# ProPrj_HydromatMK1_2025-12-27_13-47-41_2.net
KiCad netlist of a schematic drawn in EasyEDA Pro
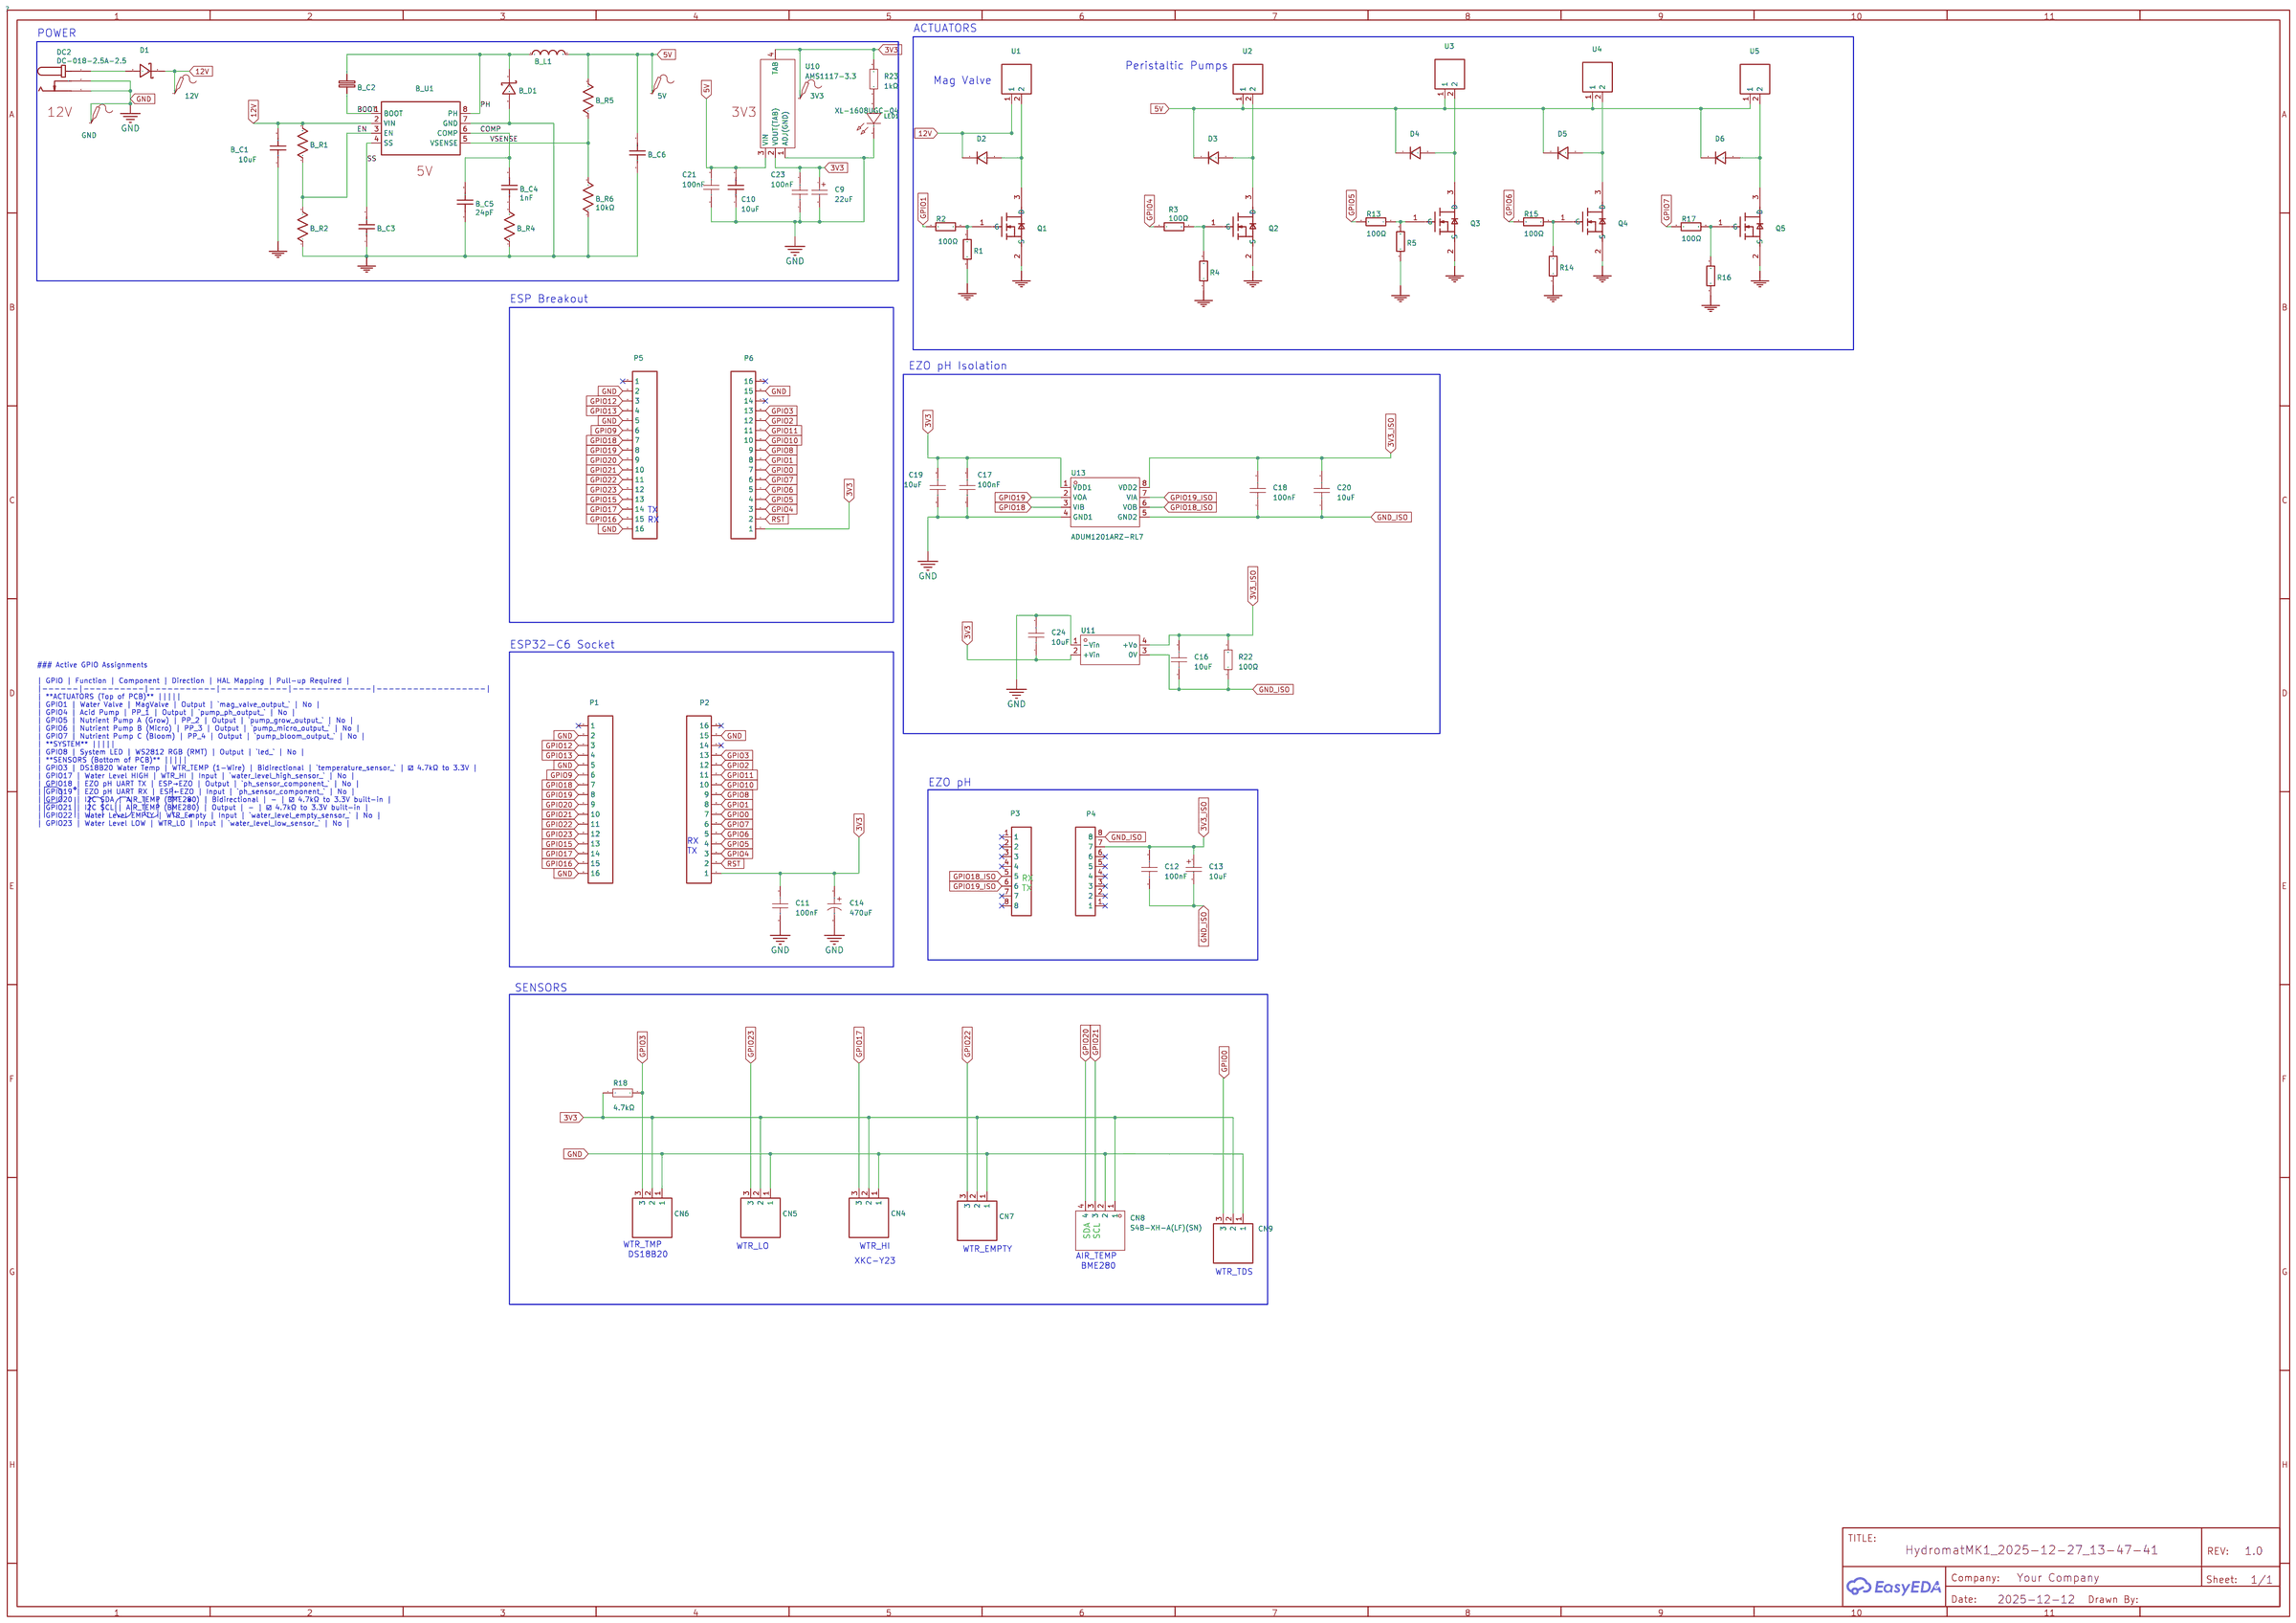
[diagram p0: schematic sheet]

(export (version "E")
  (design (tool "Eeschema 10.0.6"))
  (components
    (comp (ref "3V3")
      (value "5017")
      (footprint "easyedapro:Test-Point-0.5mm")
      (description "Test Point 测试点")
      (libsource (lib "easyedapro") (part "Test-Point"))
    )
    (comp (ref "5V")
      (value "5017")
      (footprint "easyedapro:Test-Point-0.5mm")
      (description "Test Point 测试点")
      (libsource (lib "easyedapro") (part "Test-Point"))
    )
    (comp (ref "12V")
      (value "5017")
      (footprint "easyedapro:Test-Point-0.5mm")
      (description "Test Point 测试点")
      (libsource (lib "easyedapro") (part "Test-Point"))
    )
    (comp (ref "B_C1")
      (value "10uF")
      (footprint "easyedapro:C0805")
      (fields
        (field (name "Manufacturer Part") "CL21A106KAYNNNE")
        (field (name "Manufacturer") "SAMSUNG(三星)")
      )
      (libsource (lib "easyedapro") (part "10uF"))
    )
    (comp (ref "B_C2")
      (value "100nF")
      (footprint "easyedapro:C0402")
      (fields (field (name "Manufacturer Part") "GRM155R71A104KA01D") (field (name "Manufacturer") "MuRata"))
      (libsource (lib "easyedapro") (part "100nF"))
    )
    (comp (ref "B_C3")
      (value "8.2nF")
      (footprint "easyedapro:C0201")
      (fields
        (field (name "Manufacturer Part") "GRM033R71A822KA01D")
        (field (name "Manufacturer") "MuRata")
        (field (name "Contributor") "LCEDA_Lib")
      )
      (libsource (lib "easyedapro") (part "8.2nF"))
    )
    (comp (ref "B_C4")
      (value "1nF")
      (footprint "easyedapro:C0805")
      (fields (field (name "Manufacturer Part") "GRM1555C1H102JA01J") (field (name "Manufacturer") "MuRata"))
      (libsource (lib "easyedapro") (part "1nF"))
    )
    (comp (ref "B_C5")
      (value "24pF")
      (footprint "easyedapro:C0805")
      (fields
        (field (name "Manufacturer Part") "CL21C240JBANNNC")
        (field (name "Manufacturer") "Samsung Electro-Mechanics")
      )
      (libsource (lib "easyedapro") (part "24pF"))
    )
    (comp (ref "B_C6")
      (value "10uF")
      (footprint "easyedapro:C1206")
      (fields
        (field (name "Manufacturer Part") "GRM31CR61C106KA88L")
        (field (name "Manufacturer") "MuRata")
        (field (name "Contributor") "LCEDA_Lib")
      )
      (libsource (lib "easyedapro") (part "10 uF"))
    )
    (comp (ref "B_D1")
      (value "SS24FL")
      (footprint "easyedapro:SOD-123_L2.6-W1.6-LS3.5-RD")
      (fields (field (name "Manufacturer") "KEXIN(科信)") (field (name "Contributor") "LCSC"))
      (libsource (lib "easyedapro") (part "SS24FL_C489144"))
    )
    (comp (ref "B_L1")
      (value "6.8uH")
      (footprint "easyedapro:L0805")
      (fields
        (field (name "Manufacturer Part") "74436410680")
        (field (name "Manufacturer") "Wurth Electronik")
        (field (name "Contributor") "LCEDA_Lib")
      )
      (libsource (lib "easyedapro") (part "6.8 uH"))
    )
    (comp (ref "B_R1")
      (value "169kΩ")
      (footprint "easyedapro:R0402")
      (fields
        (field (name "Manufacturer Part") "CRCW0402169KFKED")
        (field (name "Manufacturer") "Vishay-Dale")
        (field (name "Contributor") "LCEDA_Lib")
      )
      (libsource (lib "easyedapro") (part "169K"))
    )
    (comp (ref "B_R2")
      (value "39.2kΩ")
      (footprint "easyedapro:R0402")
      (fields
        (field (name "Manufacturer Part") "CRCW040239K2FKED")
        (field (name "Manufacturer") "Vishay-Dale")
        (field (name "Contributor") "LCEDA_Lib")
      )
      (libsource (lib "easyedapro") (part "39K2"))
    )
    (comp (ref "B_R4")
      (value "45.3kΩ")
      (footprint "easyedapro:R0402")
      (fields
        (field (name "Manufacturer Part") "CRCW040245K3FKED")
        (field (name "Manufacturer") "Vishay-Dale")
        (field (name "Contributor") "LCEDA_Lib")
      )
      (libsource (lib "easyedapro") (part "45K3"))
    )
    (comp (ref "B_R5")
      (value "10.2kΩ")
      (footprint "easyedapro:R0402")
      (fields
        (field (name "Manufacturer Part") "CRCW040210K2FKED")
        (field (name "Manufacturer") "Vishay-Dale")
        (field (name "Contributor") "LCEDA_Lib")
      )
      (libsource (lib "easyedapro") (part "10K2"))
    )
    (comp (ref "B_R6")
      (value "10kΩ")
      (footprint "easyedapro:R0805")
      (fields
        (field (name "Manufacturer Part") "CRCW040210K2FKED")
        (field (name "Manufacturer") "Vishay-Dale")
      )
      (libsource (lib "easyedapro") (part "1K87"))
    )
    (comp (ref "B_U1")
      (value "TPS54232DR")
      (footprint "easyedapro:SOIC-8_L4.9-W3.9-P1.27-LS6.0-BL")
      (fields (field (name "Manufacturer") "TI") (field (name "Contributor") "LCSC"))
      (libsource (lib "easyedapro") (part "TPS54232DR"))
    )
    (comp (ref "C9")
      (value "22uF")
      (footprint "easyedapro:CASE-B_3528")
      (fields (field (name "Manufacturer Part") "TAJB226K016RNJ") (field (name "Manufacturer") "Kyocera AVX"))
      (libsource (lib "easyedapro") (part "TAJB226K016RNJ"))
    )
    (comp (ref "C10")
      (value "10uF")
      (footprint "easyedapro:C0805")
      (fields
        (field (name "Manufacturer Part") "CL21A106KAYNNNE")
        (field (name "Manufacturer") "SAMSUNG(三星)")
      )
      (libsource (lib "easyedapro") (part "10uF"))
    )
    (comp (ref "C11")
      (value "100nF")
      (footprint "easyedapro:C0603")
      (description "Capacitance:100nF Tolerance:±10% Tolerance:±10% Voltage Rating:50V Temperature Coefficient:X7R")
      (fields
        (field (name "Manufacturer Part") "CC0805KRX7R9BB104")
        (field (name "Manufacturer") "YAGEO(国巨)")
      )
      (libsource (lib "easyedapro") (part "CC0603KRX7R9BB104"))
    )
    (comp (ref "C12")
      (value "100nF")
      (footprint "easyedapro:C0603")
      (description "Capacitance:100nF Tolerance:±10% Tolerance:±10% Voltage Rating:50V Temperature Coefficient:X7R")
      (fields
        (field (name "Manufacturer Part") "CC0805KRX7R9BB104")
        (field (name "Manufacturer") "YAGEO(国巨)")
      )
      (libsource (lib "easyedapro") (part "CC0603KRX7R9BB104"))
    )
    (comp (ref "C13")
      (value "10uF")
      (footprint "easyedapro:CAP-SMD_L3.2-W1.6-RD-C7171")
      (fields (field (name "Manufacturer Part") "TAJA106K016RNJ") (field (name "Manufacturer") "Kyocera AVX"))
      (libsource (lib "easyedapro") (part "TAJA106K016RNJ"))
    )
    (comp (ref "C14")
      (value "470uF")
      (footprint "easyedapro:CAP-SMD_BD6.3-L6.6-W6.6-LS7.6-RD")
      (fields (field (name "Manufacturer Part") "RVT1E471M1010") (field (name "Manufacturer") "HONOR(荣誉)"))
      (libsource (lib "easyedapro") (part "RVT1C471M0607"))
    )
    (comp (ref "C16")
      (value "10uF")
      (footprint "easyedapro:C0805")
      (fields
        (field (name "Manufacturer Part") "GRM21BR71A106KE51L")
        (field (name "Manufacturer") "muRata(村田)")
      )
      (libsource (lib "easyedapro") (part "GRM21BR71A106KE51L"))
    )
    (comp (ref "C17")
      (value "100nF")
      (footprint "easyedapro:C0603")
      (description "Capacitance:100nF Tolerance:±10% Tolerance:±10% Voltage Rating:50V Temperature Coefficient:X7R")
      (fields
        (field (name "Manufacturer Part") "CC0805KRX7R9BB104")
        (field (name "Manufacturer") "YAGEO(国巨)")
      )
      (libsource (lib "easyedapro") (part "CC0603KRX7R9BB104"))
    )
    (comp (ref "C18")
      (value "100nF")
      (footprint "easyedapro:C0603")
      (description "Capacitance:100nF Tolerance:±10% Tolerance:±10% Voltage Rating:50V Temperature Coefficient:X7R")
      (fields
        (field (name "Manufacturer Part") "CC0805KRX7R9BB104")
        (field (name "Manufacturer") "YAGEO(国巨)")
      )
      (libsource (lib "easyedapro") (part "CC0603KRX7R9BB104"))
    )
    (comp (ref "C19")
      (value "10uF")
      (footprint "easyedapro:C0805")
      (fields
        (field (name "Manufacturer Part") "GRM21BR71A106KE51L")
        (field (name "Manufacturer") "muRata(村田)")
      )
      (libsource (lib "easyedapro") (part "GRM21BR71A106KE51L"))
    )
    (comp (ref "C20")
      (value "10uF")
      (footprint "easyedapro:C0805")
      (fields
        (field (name "Manufacturer Part") "GRM21BR71A106KE51L")
        (field (name "Manufacturer") "muRata(村田)")
      )
      (libsource (lib "easyedapro") (part "GRM21BR71A106KE51L"))
    )
    (comp (ref "C21")
      (value "100nF")
      (footprint "easyedapro:C0603")
      (description "Capacitance:100nF Tolerance:±10% Tolerance:±10% Voltage Rating:50V Temperature Coefficient:X7R")
      (fields
        (field (name "Manufacturer Part") "CC0805KRX7R9BB104")
        (field (name "Manufacturer") "YAGEO(国巨)")
      )
      (libsource (lib "easyedapro") (part "CC0603KRX7R9BB104"))
    )
    (comp (ref "C23")
      (value "100nF")
      (footprint "easyedapro:C0603")
      (description "Capacitance:100nF Tolerance:±10% Tolerance:±10% Voltage Rating:50V Temperature Coefficient:X7R")
      (fields
        (field (name "Manufacturer Part") "CC0805KRX7R9BB104")
        (field (name "Manufacturer") "YAGEO(国巨)")
      )
      (libsource (lib "easyedapro") (part "CC0603KRX7R9BB104"))
    )
    (comp (ref "C24")
      (value "10uF")
      (footprint "easyedapro:C0805")
      (fields
        (field (name "Manufacturer Part") "GRM21BR71A106KE51L")
        (field (name "Manufacturer") "muRata(村田)")
      )
      (libsource (lib "easyedapro") (part "GRM21BR71A106KE51L"))
    )
    (comp (ref "CN4")
      (value "S3B-XH-A-1(LF)(SN)")
      (footprint "easyedapro:CONN-TH_S3B-XH-A-LF-SN")
      (fields
        (field (name "Manufacturer Part") "S3B-XH-A(LF)(SN)")
        (field (name "Manufacturer") "JST")
        (field (name "Contributor") "LCSC")
      )
      (libsource (lib "easyedapro") (part "S3B-XH-A (LF)(SN)"))
    )
    (comp (ref "CN5")
      (value "S3B-XH-A-1(LF)(SN)")
      (footprint "easyedapro:CONN-TH_S3B-XH-A-LF-SN")
      (fields
        (field (name "Manufacturer Part") "S3B-XH-A(LF)(SN)")
        (field (name "Manufacturer") "JST")
        (field (name "Contributor") "LCSC")
      )
      (libsource (lib "easyedapro") (part "S3B-XH-A (LF)(SN)"))
    )
    (comp (ref "CN6")
      (value "S3B-XH-A-1(LF)(SN)")
      (footprint "easyedapro:CONN-TH_S3B-XH-A-LF-SN")
      (fields
        (field (name "Manufacturer Part") "S3B-XH-A(LF)(SN)")
        (field (name "Manufacturer") "JST")
        (field (name "Contributor") "LCSC")
      )
      (libsource (lib "easyedapro") (part "S3B-XH-A (LF)(SN)"))
    )
    (comp (ref "CN7")
      (value "S3B-XH-A-1(LF)(SN)")
      (footprint "easyedapro:CONN-TH_S3B-XH-A-LF-SN")
      (fields
        (field (name "Manufacturer Part") "S3B-XH-A(LF)(SN)")
        (field (name "Manufacturer") "JST")
        (field (name "Contributor") "LCSC")
      )
      (libsource (lib "easyedapro") (part "S3B-XH-A (LF)(SN)"))
    )
    (comp (ref "CN8")
      (value "S4B-XH-A(LF)(SN)")
      (footprint "easyedapro:CONN-TH_S4B-XH-A-LF-SN")
      (fields (field (name "Manufacturer") "JST"))
      (libsource (lib "easyedapro") (part "S4B-XH-A (LF)(SN)"))
    )
    (comp (ref "CN9")
      (value "S3B-XH-A-1(LF)(SN)")
      (footprint "easyedapro:CONN-TH_S3B-XH-A-LF-SN")
      (fields
        (field (name "Manufacturer Part") "S3B-XH-A(LF)(SN)")
        (field (name "Manufacturer") "JST")
        (field (name "Contributor") "LCSC")
      )
      (libsource (lib "easyedapro") (part "S3B-XH-A (LF)(SN)"))
    )
    (comp (ref "D1")
      (value "SS54")
      (footprint "easyedapro:SMB_L4.6-W3.6-LS5.3-RD")
      (fields
        (field (name "Manufacturer Part") "MBRS140T3G")
        (field (name "Manufacturer") "onsemi(安森美)")
        (field (name "Contributor") "LCSC")
      )
      (libsource (lib "easyedapro") (part "MBRS140T3G"))
    )
    (comp (ref "D2")
      (value "SS24")
      (footprint "easyedapro:SOD-123_L2.7-W1.6-LS3.7-RD-1")
      (fields (field (name "Manufacturer Part") "1N4148W-7-F") (field (name "Manufacturer") "DIODES(美台)"))
      (libsource (lib "easyedapro") (part "1N4148W-7-F"))
    )
    (comp (ref "D3")
      (value "SS24")
      (footprint "easyedapro:SOD-123_L2.7-W1.6-LS3.7-RD-1")
      (fields (field (name "Manufacturer Part") "1N4148W-7-F") (field (name "Manufacturer") "DIODES(美台)"))
      (libsource (lib "easyedapro") (part "1N4148W-7-F"))
    )
    (comp (ref "D4")
      (value "SS24")
      (footprint "easyedapro:SOD-123_L2.7-W1.6-LS3.7-RD-1")
      (fields (field (name "Manufacturer Part") "1N4148W-7-F") (field (name "Manufacturer") "DIODES(美台)"))
      (libsource (lib "easyedapro") (part "1N4148W-7-F"))
    )
    (comp (ref "D5")
      (value "SS24")
      (footprint "easyedapro:SOD-123_L2.7-W1.6-LS3.7-RD-1")
      (fields (field (name "Manufacturer Part") "1N4148W-7-F") (field (name "Manufacturer") "DIODES(美台)"))
      (libsource (lib "easyedapro") (part "1N4148W-7-F"))
    )
    (comp (ref "D6")
      (value "SS24")
      (footprint "easyedapro:SOD-123_L2.7-W1.6-LS3.7-RD-1")
      (fields (field (name "Manufacturer Part") "1N4148W-7-F") (field (name "Manufacturer") "DIODES(美台)"))
      (libsource (lib "easyedapro") (part "1N4148W-7-F"))
    )
    (comp (ref "DC2")
      (value "DC-018-2.5A-2.5")
      (footprint "easyedapro:DC-IN-TH_DC-018")
      (fields (field (name "Manufacturer") "XKB Connection(中国星坤)") (field (name "Contributor") "lcsc"))
      (libsource (lib "easyedapro") (part "DC-018-2.5A-2.5"))
    )
    (comp (ref "GND")
      (value "5017")
      (footprint "easyedapro:Test-Point-0.5mm")
      (description "Test Point 测试点")
      (libsource (lib "easyedapro") (part "Test-Point"))
    )
    (comp (ref "LED1")
      (value "XL-1608UGC-04")
      (footprint "easyedapro:LED0603-RD_GREEN")
      (fields (field (name "Manufacturer") "XINGLIGHT(成兴光)"))
      (libsource (lib "easyedapro") (part "XL-1608UGC-04"))
    )
    (comp (ref "P1")
      (value "ZX-PM2.54-1-16PY")
      (footprint "easyedapro:HDR-TH_16P-P2.54-V-F-1")
      (fields (field (name "Manufacturer Part") "2.54-1*16P母") (field (name "Manufacturer") "BOOMELE(博穆精密)"))
      (libsource (lib "easyedapro") (part "Header-Female-2.54_1x16"))
    )
    (comp (ref "P2")
      (value "ZX-PM2.54-1-16PY")
      (footprint "easyedapro:HDR-TH_16P-P2.54-V-F-1")
      (fields (field (name "Manufacturer Part") "2.54-1*16P母") (field (name "Manufacturer") "BOOMELE(博穆精密)"))
      (libsource (lib "") (part "Header-Female-2.54_1x16_1"))
    )
    (comp (ref "P3")
      (value "2.54-1*8P母环保")
      (footprint "easyedapro:HDR-TH_8P-P2.54-V-F_2")
      (fields (field (name "Manufacturer") "BOOMELE(博穆精密)"))
      (libsource (lib "easyedapro") (part "Header-Female-2.54_1x8"))
    )
    (comp (ref "P4")
      (value "2.54-1*8P母环保")
      (footprint "easyedapro:HDR-TH_8P-P2.54-V-F_2")
      (fields (field (name "Manufacturer") "BOOMELE(博穆精密)"))
      (libsource (lib "") (part "Header-Female-2.54_1x8_1"))
    )
    (comp (ref "P5")
      (value "ZX-PM2.54-1-16PY")
      (footprint "easyedapro:HDR-TH_16P-P2.54-V-F-1")
      (fields (field (name "Manufacturer Part") "2.54-1*16P母") (field (name "Manufacturer") "BOOMELE(博穆精密)"))
      (libsource (lib "easyedapro") (part "Header-Female-2.54_1x16"))
    )
    (comp (ref "P6")
      (value "ZX-PM2.54-1-16PY")
      (footprint "easyedapro:HDR-TH_16P-P2.54-V-F-1")
      (fields (field (name "Manufacturer Part") "2.54-1*16P母") (field (name "Manufacturer") "BOOMELE(博穆精密)"))
      (libsource (lib "") (part "Header-Female-2.54_1x16_1"))
    )
    (comp (ref "Q1")
      (value "IRLML6244TRPBF")
      (footprint "easyedapro:SOT-23-3_L2.9-W1.3-P1.90-LS2.4-BR")
      (fields (field (name "Manufacturer") "TECH PUBLIC(台舟)") (field (name "Contributor") "lcsc"))
      (libsource (lib "easyedapro") (part "IRLML6244TRPBF_C5123965"))
    )
    (comp (ref "Q2")
      (value "IRLML6244TRPBF")
      (footprint "easyedapro:SOT-23-3_L2.9-W1.3-P1.90-LS2.4-BR")
      (fields (field (name "Manufacturer") "TECH PUBLIC(台舟)") (field (name "Contributor") "lcsc"))
      (libsource (lib "easyedapro") (part "IRLML6244TRPBF_C5123965"))
    )
    (comp (ref "Q3")
      (value "IRLML6244TRPBF")
      (footprint "easyedapro:SOT-23-3_L2.9-W1.3-P1.90-LS2.4-BR")
      (fields (field (name "Manufacturer") "TECH PUBLIC(台舟)") (field (name "Contributor") "lcsc"))
      (libsource (lib "easyedapro") (part "IRLML6244TRPBF_C5123965"))
    )
    (comp (ref "Q4")
      (value "IRLML6244TRPBF")
      (footprint "easyedapro:SOT-23-3_L2.9-W1.3-P1.90-LS2.4-BR")
      (fields (field (name "Manufacturer") "TECH PUBLIC(台舟)") (field (name "Contributor") "lcsc"))
      (libsource (lib "easyedapro") (part "IRLML6244TRPBF_C5123965"))
    )
    (comp (ref "Q5")
      (value "IRLML6244TRPBF")
      (footprint "easyedapro:SOT-23-3_L2.9-W1.3-P1.90-LS2.4-BR")
      (fields (field (name "Manufacturer") "TECH PUBLIC(台舟)") (field (name "Contributor") "lcsc"))
      (libsource (lib "easyedapro") (part "IRLML6244TRPBF_C5123965"))
    )
    (comp (ref "R1")
      (value "10kΩ")
      (footprint "easyedapro:R0805")
      (fields (field (name "Manufacturer Part") "RC0805JR-0710KL") (field (name "Manufacturer") "YAGEO(国巨)"))
      (libsource (lib "easyedapro") (part "10kΩ"))
    )
    (comp (ref "R2")
      (value "100Ω")
      (footprint "easyedapro:R0805")
      (fields
        (field (name "Manufacturer Part") "0805W8F330JT5E")
        (field (name "Manufacturer") "UNI-ROYAL(厚声)")
      )
      (libsource (lib "easyedapro") (part "33Ω"))
    )
    (comp (ref "R3")
      (value "100Ω")
      (footprint "easyedapro:R0805")
      (fields
        (field (name "Manufacturer Part") "0805W8F330JT5E")
        (field (name "Manufacturer") "UNI-ROYAL(厚声)")
      )
      (libsource (lib "") (part "33Ω_1"))
    )
    (comp (ref "R4")
      (value "10kΩ")
      (footprint "easyedapro:R0805")
      (fields (field (name "Manufacturer Part") "RC0805JR-0710KL") (field (name "Manufacturer") "YAGEO(国巨)"))
      (libsource (lib "easyedapro") (part "10kΩ"))
    )
    (comp (ref "R5")
      (value "10kΩ")
      (footprint "easyedapro:R0805")
      (fields (field (name "Manufacturer Part") "RC0805JR-0710KL") (field (name "Manufacturer") "YAGEO(国巨)"))
      (libsource (lib "easyedapro") (part "10kΩ"))
    )
    (comp (ref "R13")
      (value "100Ω")
      (footprint "easyedapro:R0805")
      (fields
        (field (name "Manufacturer Part") "0805W8F330JT5E")
        (field (name "Manufacturer") "UNI-ROYAL(厚声)")
      )
      (libsource (lib "easyedapro") (part "33Ω"))
    )
    (comp (ref "R14")
      (value "10kΩ")
      (footprint "easyedapro:R0805")
      (fields (field (name "Manufacturer Part") "RC0805JR-0710KL") (field (name "Manufacturer") "YAGEO(国巨)"))
      (libsource (lib "easyedapro") (part "10kΩ"))
    )
    (comp (ref "R15")
      (value "100Ω")
      (footprint "easyedapro:R0805")
      (fields
        (field (name "Manufacturer Part") "0805W8F330JT5E")
        (field (name "Manufacturer") "UNI-ROYAL(厚声)")
      )
      (libsource (lib "easyedapro") (part "33Ω"))
    )
    (comp (ref "R16")
      (value "10kΩ")
      (footprint "easyedapro:R0805")
      (fields (field (name "Manufacturer Part") "RC0805JR-0710KL") (field (name "Manufacturer") "YAGEO(国巨)"))
      (libsource (lib "easyedapro") (part "10kΩ"))
    )
    (comp (ref "R17")
      (value "100Ω")
      (footprint "easyedapro:R0805")
      (fields
        (field (name "Manufacturer Part") "0805W8F330JT5E")
        (field (name "Manufacturer") "UNI-ROYAL(厚声)")
      )
      (libsource (lib "easyedapro") (part "33Ω"))
    )
    (comp (ref "R18")
      (value "4.7kΩ")
      (footprint "easyedapro:R0603")
      (fields
        (field (name "Manufacturer Part") "0805W8F4701T5E")
        (field (name "Manufacturer") "UNI-ROYAL(厚声)")
      )
      (libsource (lib "easyedapro") (part "RC0603FR-074K7L"))
    )
    (comp (ref "R22")
      (value "100Ω")
      (footprint "easyedapro:R0603")
      (fields
        (field (name "Manufacturer Part") "0805W8F1000T5E")
        (field (name "Manufacturer") "UNI-ROYAL(厚声)")
      )
      (libsource (lib "easyedapro") (part "0603WAF1000T5E"))
    )
    (comp (ref "R23")
      (value "1kΩ")
      (footprint "easyedapro:R0603")
      (fields (field (name "Manufacturer Part") "FRC0805J102 TS") (field (name "Manufacturer") "FOJAN(富捷)"))
      (libsource (lib "easyedapro") (part "0603WAF1001T5E"))
    )
    (comp (ref "U1")
      (value "S2B-XH-A-1(LF)(SN)")
      (footprint "easyedapro:CONN-TH_S2B-XH-A-LF-SN")
      (fields
        (field (name "Manufacturer Part") "S2B-XH-A(LF)(SN)")
        (field (name "Manufacturer") "JST")
        (field (name "Contributor") "LCSC")
      )
      (libsource (lib "easyedapro") (part "S2B-XH-A-(LF)(SN)"))
    )
    (comp (ref "U2")
      (value "S2B-XH-A-1(LF)(SN)")
      (footprint "easyedapro:CONN-TH_S2B-XH-A-LF-SN")
      (fields
        (field (name "Manufacturer Part") "S2B-XH-A(LF)(SN)")
        (field (name "Manufacturer") "JST")
        (field (name "Contributor") "LCSC")
      )
      (libsource (lib "easyedapro") (part "S2B-XH-A-(LF)(SN)"))
    )
    (comp (ref "U3")
      (value "S2B-XH-A-1(LF)(SN)")
      (footprint "easyedapro:CONN-TH_S2B-XH-A-LF-SN")
      (fields
        (field (name "Manufacturer Part") "S2B-XH-A(LF)(SN)")
        (field (name "Manufacturer") "JST")
        (field (name "Contributor") "LCSC")
      )
      (libsource (lib "easyedapro") (part "S2B-XH-A-(LF)(SN)"))
    )
    (comp (ref "U4")
      (value "S2B-XH-A-1(LF)(SN)")
      (footprint "easyedapro:CONN-TH_S2B-XH-A-LF-SN")
      (fields
        (field (name "Manufacturer Part") "S2B-XH-A(LF)(SN)")
        (field (name "Manufacturer") "JST")
        (field (name "Contributor") "LCSC")
      )
      (libsource (lib "easyedapro") (part "S2B-XH-A-(LF)(SN)"))
    )
    (comp (ref "U5")
      (value "S2B-XH-A-1(LF)(SN)")
      (footprint "easyedapro:CONN-TH_S2B-XH-A-LF-SN")
      (fields
        (field (name "Manufacturer Part") "S2B-XH-A(LF)(SN)")
        (field (name "Manufacturer") "JST")
        (field (name "Contributor") "LCSC")
      )
      (libsource (lib "easyedapro") (part "S2B-XH-A-(LF)(SN)"))
    )
    (comp (ref "U10")
      (value "AMS1117-3.3")
      (footprint "easyedapro:SOT-223-4_L6.5-W3.5-P2.30-LS7.0-BR")
      (fields (field (name "Manufacturer") "UMW(友台半导体)"))
      (libsource (lib "easyedapro") (part "AMS1117-3.3_C347222"))
    )
    (comp (ref "U11")
      (value "220kHz")
      (footprint "easyedapro:PWRM-TH_B0303S-1WR3")
      (fields (field (name "Manufacturer Part") "B0303S-1WR3") (field (name "Manufacturer") "YLPTEC(易川)"))
      (libsource (lib "easyedapro") (part "B0303S-1WR3_C7468813"))
    )
    (comp (ref "U13")
      (value "ADUM1201ARZ-RL7")
      (footprint "easyedapro:SOIC-8_L4.9-W3.9-P1.27-LS6.0-BL")
      (fields (field (name "Manufacturer") "ADI(亚德诺)"))
      (libsource (lib "easyedapro") (part "ADUM1201ARZ-RL7"))
    )
  )
  (nets
    (net (code "1") (name "/BOOT") (class "Default")
      (node (ref "B_C2") (pin "2") (pinfunction "2_2") (pintype "bidirectional"))
      (node (ref "B_U1") (pin "1") (pinfunction "BOOT_1") (pintype "unspecified"))
    )
    (net (code "2") (name "/COMP") (class "Default")
      (node (ref "B_C4") (pin "2") (pinfunction "2_2") (pintype "unspecified"))
      (node (ref "B_C5") (pin "2") (pinfunction "2_2") (pintype "unspecified"))
      (node (ref "B_U1") (pin "6") (pinfunction "COMP_6") (pintype "unspecified"))
    )
    (net (code "3") (name "/EN") (class "Default")
      (node (ref "B_R1") (pin "1") (pinfunction "1_1") (pintype "unspecified"))
      (node (ref "B_R2") (pin "2") (pinfunction "2_2") (pintype "unspecified"))
      (node (ref "B_U1") (pin "3") (pinfunction "EN_3") (pintype "unspecified"))
    )
    (net (code "4") (name "/PH") (class "Default")
      (node (ref "B_C2") (pin "1") (pinfunction "1_1") (pintype "bidirectional"))
      (node (ref "B_D1") (pin "1") (pinfunction "K_1") (pintype "unspecified"))
      (node (ref "B_L1") (pin "1") (pinfunction "1_1") (pintype "unspecified"))
      (node (ref "B_U1") (pin "8") (pinfunction "PH_8") (pintype "unspecified"))
    )
    (net (code "5") (name "/SS") (class "Default")
      (node (ref "B_C3") (pin "2") (pinfunction "2_2") (pintype "unspecified"))
      (node (ref "B_U1") (pin "4") (pinfunction "SS_4") (pintype "unspecified"))
    )
    (net (code "6") (name "/VSENSE") (class "Default")
      (node (ref "B_R5") (pin "1") (pinfunction "1_1") (pintype "unspecified"))
      (node (ref "B_R6") (pin "2") (pinfunction "2_2") (pintype "unspecified"))
      (node (ref "B_U1") (pin "5") (pinfunction "VSENSE_5") (pintype "unspecified"))
    )
    (net (code "7") (name "3V3") (class "Default")
      (node (ref "3V3") (pin "1") (pinfunction "1_1") (pintype "unspecified"))
      (node (ref "C11") (pin "2") (pinfunction "2_2") (pintype "unspecified"))
      (node (ref "C14") (pin "1") (pinfunction "1_1") (pintype "input"))
      (node (ref "C17") (pin "2") (pinfunction "2_2") (pintype "unspecified"))
      (node (ref "C19") (pin "2") (pinfunction "2_2") (pintype "unspecified"))
      (node (ref "C23") (pin "2") (pinfunction "2_2") (pintype "unspecified"))
      (node (ref "C24") (pin "1") (pinfunction "1_1") (pintype "unspecified"))
      (node (ref "C9") (pin "1") (pinfunction "1_1") (pintype "input"))
      (node (ref "CN4") (pin "2") (pinfunction "2_2") (pintype "unspecified"))
      (node (ref "CN5") (pin "2") (pinfunction "2_2") (pintype "unspecified"))
      (node (ref "CN6") (pin "2") (pinfunction "2_2") (pintype "unspecified"))
      (node (ref "CN7") (pin "2") (pinfunction "2_2") (pintype "unspecified"))
      (node (ref "CN8") (pin "1") (pinfunction "1_1") (pintype "unspecified"))
      (node (ref "CN9") (pin "2") (pinfunction "2_2") (pintype "unspecified"))
      (node (ref "P2") (pin "1") (pinfunction "1_1") (pintype "input"))
      (node (ref "P6") (pin "1") (pinfunction "1_1") (pintype "input"))
      (node (ref "R18") (pin "1") (pinfunction "1_1") (pintype "input"))
      (node (ref "R23") (pin "2") (pinfunction "2_2") (pintype "input"))
      (node (ref "U10") (pin "2") (pinfunction "VOUT(TAB)_2") (pintype "unspecified"))
      (node (ref "U10") (pin "4") (pinfunction "TAB_4") (pintype "unspecified"))
      (node (ref "U11") (pin "2") (pinfunction "+Vin_2") (pintype "unspecified"))
      (node (ref "U13") (pin "1") (pinfunction "VDD1_1") (pintype "unspecified"))
    )
    (net (code "8") (name "3V3_ISO") (class "Default")
      (node (ref "C12") (pin "2") (pinfunction "2_2") (pintype "unspecified"))
      (node (ref "C13") (pin "1") (pinfunction "1_1") (pintype "input"))
      (node (ref "C16") (pin "2") (pinfunction "2_2") (pintype "unspecified"))
      (node (ref "C18") (pin "2") (pinfunction "2_2") (pintype "unspecified"))
      (node (ref "C20") (pin "2") (pinfunction "2_2") (pintype "unspecified"))
      (node (ref "P4") (pin "7") (pinfunction "7_7") (pintype "unspecified"))
      (node (ref "R22") (pin "2") (pinfunction "2_2") (pintype "input"))
      (node (ref "U11") (pin "4") (pinfunction "+Vo_4") (pintype "unspecified"))
      (node (ref "U13") (pin "8") (pinfunction "VDD2_8") (pintype "unspecified"))
    )
    (net (code "9") (name "5V") (class "Default")
      (node (ref "5V") (pin "1") (pinfunction "1_1") (pintype "unspecified"))
      (node (ref "B_C6") (pin "2") (pinfunction "2_2") (pintype "unspecified"))
      (node (ref "B_L1") (pin "2") (pinfunction "2_2") (pintype "unspecified"))
      (node (ref "B_R5") (pin "2") (pinfunction "2_2") (pintype "unspecified"))
      (node (ref "C10") (pin "2") (pinfunction "2_2") (pintype "unspecified"))
      (node (ref "C21") (pin "2") (pinfunction "2_2") (pintype "unspecified"))
      (node (ref "D3") (pin "1") (pinfunction "C_1") (pintype "unspecified"))
      (node (ref "D4") (pin "1") (pinfunction "C_1") (pintype "unspecified"))
      (node (ref "D5") (pin "1") (pinfunction "C_1") (pintype "unspecified"))
      (node (ref "D6") (pin "1") (pinfunction "C_1") (pintype "unspecified"))
      (node (ref "U10") (pin "3") (pinfunction "VIN_3") (pintype "unspecified"))
      (node (ref "U2") (pin "1") (pinfunction "1_1") (pintype "unspecified"))
      (node (ref "U3") (pin "1") (pinfunction "1_1") (pintype "unspecified"))
      (node (ref "U4") (pin "1") (pinfunction "1_1") (pintype "unspecified"))
      (node (ref "U5") (pin "1") (pinfunction "1_1") (pintype "unspecified"))
    )
    (net (code "10") (name "12V") (class "Default")
      (node (ref "12V") (pin "1") (pinfunction "1_1") (pintype "unspecified"))
      (node (ref "B_C1") (pin "2") (pinfunction "2_2") (pintype "unspecified"))
      (node (ref "B_R1") (pin "2") (pinfunction "2_2") (pintype "unspecified"))
      (node (ref "B_U1") (pin "2") (pinfunction "VIN_2") (pintype "unspecified"))
      (node (ref "D1") (pin "1") (pinfunction "K_1") (pintype "unspecified"))
      (node (ref "D2") (pin "1") (pinfunction "C_1") (pintype "unspecified"))
      (node (ref "U1") (pin "1") (pinfunction "1_1") (pintype "unspecified"))
    )
    (net (code "11") (name "GND") (class "Default")
      (node (ref "B_C1") (pin "1") (pinfunction "1_1") (pintype "unspecified"))
      (node (ref "B_C3") (pin "1") (pinfunction "1_1") (pintype "unspecified"))
      (node (ref "B_C5") (pin "1") (pinfunction "1_1") (pintype "unspecified"))
      (node (ref "B_C6") (pin "1") (pinfunction "1_1") (pintype "unspecified"))
      (node (ref "B_D1") (pin "2") (pinfunction "A_2") (pintype "unspecified"))
      (node (ref "B_R2") (pin "1") (pinfunction "1_1") (pintype "unspecified"))
      (node (ref "B_R4") (pin "1") (pinfunction "1_1") (pintype "unspecified"))
      (node (ref "B_R6") (pin "1") (pinfunction "1_1") (pintype "unspecified"))
      (node (ref "B_U1") (pin "7") (pinfunction "GND_7") (pintype "unspecified"))
      (node (ref "C10") (pin "1") (pinfunction "1_1") (pintype "unspecified"))
      (node (ref "C11") (pin "1") (pinfunction "1_1") (pintype "unspecified"))
      (node (ref "C14") (pin "2") (pinfunction "2_2") (pintype "input"))
      (node (ref "C17") (pin "1") (pinfunction "1_1") (pintype "unspecified"))
      (node (ref "C19") (pin "1") (pinfunction "1_1") (pintype "unspecified"))
      (node (ref "C21") (pin "1") (pinfunction "1_1") (pintype "unspecified"))
      (node (ref "C23") (pin "1") (pinfunction "1_1") (pintype "unspecified"))
      (node (ref "C24") (pin "2") (pinfunction "2_2") (pintype "unspecified"))
      (node (ref "C9") (pin "2") (pinfunction "2_2") (pintype "input"))
      (node (ref "CN4") (pin "1") (pinfunction "1_1") (pintype "unspecified"))
      (node (ref "CN5") (pin "1") (pinfunction "1_1") (pintype "unspecified"))
      (node (ref "CN6") (pin "1") (pinfunction "1_1") (pintype "unspecified"))
      (node (ref "CN7") (pin "1") (pinfunction "1_1") (pintype "unspecified"))
      (node (ref "CN8") (pin "2") (pinfunction "2_2") (pintype "unspecified"))
      (node (ref "CN9") (pin "1") (pinfunction "1_1") (pintype "unspecified"))
      (node (ref "DC2") (pin "2") (pinfunction "2_2") (pintype "unspecified"))
      (node (ref "DC2") (pin "3") (pinfunction "3_3") (pintype "unspecified"))
      (node (ref "GND") (pin "1") (pinfunction "1_1") (pintype "unspecified"))
      (node (ref "LED1") (pin "1") (pinfunction "K_1") (pintype "input"))
      (node (ref "P1") (pin "16") (pinfunction "16_16") (pintype "input"))
      (node (ref "P1") (pin "2") (pinfunction "2_2") (pintype "input"))
      (node (ref "P1") (pin "5") (pinfunction "5_5") (pintype "input"))
      (node (ref "P2") (pin "15") (pinfunction "15_15") (pintype "input"))
      (node (ref "P5") (pin "16") (pinfunction "16_16") (pintype "input"))
      (node (ref "P5") (pin "2") (pinfunction "2_2") (pintype "input"))
      (node (ref "P5") (pin "5") (pinfunction "5_5") (pintype "input"))
      (node (ref "P6") (pin "15") (pinfunction "15_15") (pintype "input"))
      (node (ref "Q1") (pin "2") (pinfunction "S_2") (pintype "unspecified"))
      (node (ref "Q2") (pin "2") (pinfunction "S_2") (pintype "unspecified"))
      (node (ref "Q3") (pin "2") (pinfunction "S_2") (pintype "unspecified"))
      (node (ref "Q4") (pin "2") (pinfunction "S_2") (pintype "unspecified"))
      (node (ref "Q5") (pin "2") (pinfunction "S_2") (pintype "unspecified"))
      (node (ref "R1") (pin "1") (pinfunction "1_1") (pintype "input"))
      (node (ref "R14") (pin "1") (pinfunction "1_1") (pintype "input"))
      (node (ref "R16") (pin "1") (pinfunction "1_1") (pintype "input"))
      (node (ref "R4") (pin "1") (pinfunction "1_1") (pintype "input"))
      (node (ref "R5") (pin "1") (pinfunction "1_1") (pintype "input"))
      (node (ref "U10") (pin "1") (pinfunction "ADJ(GND)_1") (pintype "unspecified"))
      (node (ref "U11") (pin "1") (pinfunction "-Vin_1") (pintype "unspecified"))
      (node (ref "U13") (pin "4") (pinfunction "GND1_4") (pintype "unspecified"))
    )
    (net (code "12") (name "GND_ISO") (class "Default")
      (node (ref "C12") (pin "1") (pinfunction "1_1") (pintype "unspecified"))
      (node (ref "C13") (pin "2") (pinfunction "2_2") (pintype "input"))
      (node (ref "C16") (pin "1") (pinfunction "1_1") (pintype "unspecified"))
      (node (ref "C18") (pin "1") (pinfunction "1_1") (pintype "unspecified"))
      (node (ref "C20") (pin "1") (pinfunction "1_1") (pintype "unspecified"))
      (node (ref "P4") (pin "8") (pinfunction "8_8") (pintype "unspecified"))
      (node (ref "R22") (pin "1") (pinfunction "1_1") (pintype "input"))
      (node (ref "U11") (pin "3") (pinfunction "0V_3") (pintype "unspecified"))
      (node (ref "U13") (pin "5") (pinfunction "GND2_5") (pintype "unspecified"))
    )
    (net (code "13") (name "GPIO0") (class "Default")
      (node (ref "CN9") (pin "3") (pinfunction "3_3") (pintype "unspecified"))
      (node (ref "P2") (pin "7") (pinfunction "7_7") (pintype "input"))
      (node (ref "P6") (pin "7") (pinfunction "7_7") (pintype "input"))
    )
    (net (code "14") (name "GPIO1") (class "Default")
      (node (ref "P2") (pin "8") (pinfunction "8_8") (pintype "input"))
      (node (ref "P6") (pin "8") (pinfunction "8_8") (pintype "input"))
      (node (ref "R2") (pin "1") (pinfunction "1_1") (pintype "input"))
    )
    (net (code "15") (name "GPIO2") (class "Default")
      (node (ref "P2") (pin "12") (pinfunction "12_12") (pintype "input"))
      (node (ref "P6") (pin "12") (pinfunction "12_12") (pintype "input"))
    )
    (net (code "16") (name "GPIO3") (class "Default")
      (node (ref "CN6") (pin "3") (pinfunction "3_3") (pintype "unspecified"))
      (node (ref "P2") (pin "13") (pinfunction "13_13") (pintype "input"))
      (node (ref "P6") (pin "13") (pinfunction "13_13") (pintype "input"))
      (node (ref "R18") (pin "2") (pinfunction "2_2") (pintype "input"))
    )
    (net (code "17") (name "GPIO4") (class "Default")
      (node (ref "P2") (pin "3") (pinfunction "3_3") (pintype "input"))
      (node (ref "P6") (pin "3") (pinfunction "3_3") (pintype "input"))
      (node (ref "R3") (pin "2") (pinfunction "2_2") (pintype "input"))
    )
    (net (code "18") (name "GPIO5") (class "Default")
      (node (ref "P2") (pin "4") (pinfunction "4_4") (pintype "input"))
      (node (ref "P6") (pin "4") (pinfunction "4_4") (pintype "input"))
      (node (ref "R13") (pin "2") (pinfunction "2_2") (pintype "input"))
    )
    (net (code "19") (name "GPIO6") (class "Default")
      (node (ref "P2") (pin "5") (pinfunction "5_5") (pintype "input"))
      (node (ref "P6") (pin "5") (pinfunction "5_5") (pintype "input"))
      (node (ref "R15") (pin "2") (pinfunction "2_2") (pintype "input"))
    )
    (net (code "20") (name "GPIO7") (class "Default")
      (node (ref "P2") (pin "6") (pinfunction "6_6") (pintype "input"))
      (node (ref "P6") (pin "6") (pinfunction "6_6") (pintype "input"))
      (node (ref "R17") (pin "1") (pinfunction "1_1") (pintype "input"))
    )
    (net (code "21") (name "GPIO8") (class "Default")
      (node (ref "P2") (pin "9") (pinfunction "9_9") (pintype "input"))
      (node (ref "P6") (pin "9") (pinfunction "9_9") (pintype "input"))
    )
    (net (code "22") (name "GPIO9") (class "Default")
      (node (ref "P1") (pin "6") (pinfunction "6_6") (pintype "input"))
      (node (ref "P5") (pin "6") (pinfunction "6_6") (pintype "input"))
    )
    (net (code "23") (name "GPIO10") (class "Default")
      (node (ref "P2") (pin "10") (pinfunction "10_10") (pintype "input"))
      (node (ref "P6") (pin "10") (pinfunction "10_10") (pintype "input"))
    )
    (net (code "24") (name "GPIO11") (class "Default")
      (node (ref "P2") (pin "11") (pinfunction "11_11") (pintype "input"))
      (node (ref "P6") (pin "11") (pinfunction "11_11") (pintype "input"))
    )
    (net (code "25") (name "GPIO12") (class "Default")
      (node (ref "P1") (pin "3") (pinfunction "3_3") (pintype "input"))
      (node (ref "P5") (pin "3") (pinfunction "3_3") (pintype "input"))
    )
    (net (code "26") (name "GPIO13") (class "Default")
      (node (ref "P1") (pin "4") (pinfunction "4_4") (pintype "input"))
      (node (ref "P5") (pin "4") (pinfunction "4_4") (pintype "input"))
    )
    (net (code "27") (name "GPIO15") (class "Default")
      (node (ref "P1") (pin "13") (pinfunction "13_13") (pintype "input"))
      (node (ref "P5") (pin "13") (pinfunction "13_13") (pintype "input"))
    )
    (net (code "28") (name "GPIO16") (class "Default")
      (node (ref "P1") (pin "15") (pinfunction "15_15") (pintype "input"))
      (node (ref "P5") (pin "15") (pinfunction "15_15") (pintype "input"))
    )
    (net (code "29") (name "GPIO17") (class "Default")
      (node (ref "CN4") (pin "3") (pinfunction "3_3") (pintype "unspecified"))
      (node (ref "P1") (pin "14") (pinfunction "14_14") (pintype "input"))
      (node (ref "P5") (pin "14") (pinfunction "14_14") (pintype "input"))
    )
    (net (code "30") (name "GPIO18") (class "Default")
      (node (ref "P1") (pin "7") (pinfunction "7_7") (pintype "input"))
      (node (ref "P5") (pin "7") (pinfunction "7_7") (pintype "input"))
      (node (ref "U13") (pin "3") (pinfunction "VIB_3") (pintype "unspecified"))
    )
    (net (code "31") (name "GPIO18_ISO") (class "Default")
      (node (ref "P3") (pin "5") (pinfunction "5_5") (pintype "unspecified"))
      (node (ref "U13") (pin "6") (pinfunction "VOB_6") (pintype "unspecified"))
    )
    (net (code "32") (name "GPIO19") (class "Default")
      (node (ref "P1") (pin "8") (pinfunction "8_8") (pintype "input"))
      (node (ref "P5") (pin "8") (pinfunction "8_8") (pintype "input"))
      (node (ref "U13") (pin "2") (pinfunction "VOA_2") (pintype "unspecified"))
    )
    (net (code "33") (name "GPIO19_ISO") (class "Default")
      (node (ref "P3") (pin "6") (pinfunction "6_6") (pintype "unspecified"))
      (node (ref "U13") (pin "7") (pinfunction "VIA_7") (pintype "unspecified"))
    )
    (net (code "34") (name "GPIO20") (class "Default")
      (node (ref "CN8") (pin "4") (pinfunction "4_4") (pintype "unspecified"))
      (node (ref "P1") (pin "9") (pinfunction "9_9") (pintype "input"))
      (node (ref "P5") (pin "9") (pinfunction "9_9") (pintype "input"))
    )
    (net (code "35") (name "GPIO21") (class "Default")
      (node (ref "CN8") (pin "3") (pinfunction "3_3") (pintype "unspecified"))
      (node (ref "P1") (pin "10") (pinfunction "10_10") (pintype "input"))
      (node (ref "P5") (pin "10") (pinfunction "10_10") (pintype "input"))
    )
    (net (code "36") (name "GPIO22") (class "Default")
      (node (ref "CN7") (pin "3") (pinfunction "3_3") (pintype "unspecified"))
      (node (ref "P1") (pin "11") (pinfunction "11_11") (pintype "input"))
      (node (ref "P5") (pin "11") (pinfunction "11_11") (pintype "input"))
    )
    (net (code "37") (name "GPIO23") (class "Default")
      (node (ref "CN5") (pin "3") (pinfunction "3_3") (pintype "unspecified"))
      (node (ref "P1") (pin "12") (pinfunction "12_12") (pintype "input"))
      (node (ref "P5") (pin "12") (pinfunction "12_12") (pintype "input"))
    )
    (net (code "38") (name "Net-(B_C4-Pad1)") (class "Default")
      (node (ref "B_C4") (pin "1") (pinfunction "1_1") (pintype "unspecified"))
      (node (ref "B_R4") (pin "2") (pinfunction "2_2") (pintype "unspecified"))
    )
    (net (code "39") (name "Net-(D1-A)") (class "Default")
      (node (ref "D1") (pin "2") (pinfunction "A_2") (pintype "unspecified"))
      (node (ref "DC2") (pin "1") (pinfunction "1_1") (pintype "unspecified"))
    )
    (net (code "40") (name "Net-(D2-A)") (class "Default")
      (node (ref "D2") (pin "2") (pinfunction "A_2") (pintype "unspecified"))
      (node (ref "Q1") (pin "3") (pinfunction "D_3") (pintype "unspecified"))
      (node (ref "U1") (pin "2") (pinfunction "2_2") (pintype "unspecified"))
    )
    (net (code "41") (name "Net-(D3-A)") (class "Default")
      (node (ref "D3") (pin "2") (pinfunction "A_2") (pintype "unspecified"))
      (node (ref "Q2") (pin "3") (pinfunction "D_3") (pintype "unspecified"))
      (node (ref "U2") (pin "2") (pinfunction "2_2") (pintype "unspecified"))
    )
    (net (code "42") (name "Net-(D4-A)") (class "Default")
      (node (ref "D4") (pin "2") (pinfunction "A_2") (pintype "unspecified"))
      (node (ref "Q3") (pin "3") (pinfunction "D_3") (pintype "unspecified"))
      (node (ref "U3") (pin "2") (pinfunction "2_2") (pintype "unspecified"))
    )
    (net (code "43") (name "Net-(D5-A)") (class "Default")
      (node (ref "D5") (pin "2") (pinfunction "A_2") (pintype "unspecified"))
      (node (ref "Q4") (pin "3") (pinfunction "D_3") (pintype "unspecified"))
      (node (ref "U4") (pin "2") (pinfunction "2_2") (pintype "unspecified"))
    )
    (net (code "44") (name "Net-(D6-A)") (class "Default")
      (node (ref "D6") (pin "2") (pinfunction "A_2") (pintype "unspecified"))
      (node (ref "Q5") (pin "3") (pinfunction "D_3") (pintype "unspecified"))
      (node (ref "U5") (pin "2") (pinfunction "2_2") (pintype "unspecified"))
    )
    (net (code "45") (name "Net-(LED1-A)") (class "Default")
      (node (ref "LED1") (pin "2") (pinfunction "A_2") (pintype "input"))
      (node (ref "R23") (pin "1") (pinfunction "1_1") (pintype "input"))
    )
    (net (code "46") (name "Net-(Q1-G)") (class "Default")
      (node (ref "Q1") (pin "1") (pinfunction "G_1") (pintype "unspecified"))
      (node (ref "R1") (pin "2") (pinfunction "2_2") (pintype "input"))
      (node (ref "R2") (pin "2") (pinfunction "2_2") (pintype "input"))
    )
    (net (code "47") (name "Net-(Q2-G)") (class "Default")
      (node (ref "Q2") (pin "1") (pinfunction "G_1") (pintype "unspecified"))
      (node (ref "R3") (pin "1") (pinfunction "1_1") (pintype "input"))
      (node (ref "R4") (pin "2") (pinfunction "2_2") (pintype "input"))
    )
    (net (code "48") (name "Net-(Q3-G)") (class "Default")
      (node (ref "Q3") (pin "1") (pinfunction "G_1") (pintype "unspecified"))
      (node (ref "R13") (pin "1") (pinfunction "1_1") (pintype "input"))
      (node (ref "R5") (pin "2") (pinfunction "2_2") (pintype "input"))
    )
    (net (code "49") (name "Net-(Q4-G)") (class "Default")
      (node (ref "Q4") (pin "1") (pinfunction "G_1") (pintype "unspecified"))
      (node (ref "R14") (pin "2") (pinfunction "2_2") (pintype "input"))
      (node (ref "R15") (pin "1") (pinfunction "1_1") (pintype "input"))
    )
    (net (code "50") (name "Net-(Q5-G)") (class "Default")
      (node (ref "Q5") (pin "1") (pinfunction "G_1") (pintype "unspecified"))
      (node (ref "R16") (pin "2") (pinfunction "2_2") (pintype "input"))
      (node (ref "R17") (pin "2") (pinfunction "2_2") (pintype "input"))
    )
    (net (code "51") (name "RST") (class "Default")
      (node (ref "P2") (pin "2") (pinfunction "2_2") (pintype "input"))
      (node (ref "P6") (pin "2") (pinfunction "2_2") (pintype "input"))
    )
    (net (code "52") (name "unconnected-(P1-Pad1)") (class "Default")
      (node (ref "P1") (pin "1") (pinfunction "1_1") (pintype "input+no_connect"))
    )
    (net (code "53") (name "unconnected-(P2-Pad14)") (class "Default")
      (node (ref "P2") (pin "14") (pinfunction "14_14") (pintype "input+no_connect"))
    )
    (net (code "54") (name "unconnected-(P2-Pad16)") (class "Default")
      (node (ref "P2") (pin "16") (pinfunction "16_16") (pintype "input+no_connect"))
    )
    (net (code "55") (name "unconnected-(P3-Pad1)") (class "Default")
      (node (ref "P3") (pin "1") (pinfunction "1_1") (pintype "unspecified+no_connect"))
    )
    (net (code "56") (name "unconnected-(P3-Pad2)") (class "Default")
      (node (ref "P3") (pin "2") (pinfunction "2_2") (pintype "unspecified+no_connect"))
    )
    (net (code "57") (name "unconnected-(P3-Pad3)") (class "Default")
      (node (ref "P3") (pin "3") (pinfunction "3_3") (pintype "unspecified+no_connect"))
    )
    (net (code "58") (name "unconnected-(P3-Pad4)") (class "Default")
      (node (ref "P3") (pin "4") (pinfunction "4_4") (pintype "unspecified+no_connect"))
    )
    (net (code "59") (name "unconnected-(P3-Pad7)") (class "Default")
      (node (ref "P3") (pin "7") (pinfunction "7_7") (pintype "unspecified+no_connect"))
    )
    (net (code "60") (name "unconnected-(P3-Pad8)") (class "Default")
      (node (ref "P3") (pin "8") (pinfunction "8_8") (pintype "unspecified+no_connect"))
    )
    (net (code "61") (name "unconnected-(P4-Pad1)") (class "Default")
      (node (ref "P4") (pin "1") (pinfunction "1_1") (pintype "unspecified+no_connect"))
    )
    (net (code "62") (name "unconnected-(P4-Pad2)") (class "Default")
      (node (ref "P4") (pin "2") (pinfunction "2_2") (pintype "unspecified+no_connect"))
    )
    (net (code "63") (name "unconnected-(P4-Pad3)") (class "Default")
      (node (ref "P4") (pin "3") (pinfunction "3_3") (pintype "unspecified+no_connect"))
    )
    (net (code "64") (name "unconnected-(P4-Pad4)") (class "Default")
      (node (ref "P4") (pin "4") (pinfunction "4_4") (pintype "unspecified+no_connect"))
    )
    (net (code "65") (name "unconnected-(P4-Pad5)") (class "Default")
      (node (ref "P4") (pin "5") (pinfunction "5_5") (pintype "unspecified+no_connect"))
    )
    (net (code "66") (name "unconnected-(P4-Pad6)") (class "Default")
      (node (ref "P4") (pin "6") (pinfunction "6_6") (pintype "unspecified+no_connect"))
    )
    (net (code "67") (name "unconnected-(P5-Pad1)") (class "Default")
      (node (ref "P5") (pin "1") (pinfunction "1_1") (pintype "input+no_connect"))
    )
    (net (code "68") (name "unconnected-(P6-Pad14)") (class "Default")
      (node (ref "P6") (pin "14") (pinfunction "14_14") (pintype "input+no_connect"))
    )
    (net (code "69") (name "unconnected-(P6-Pad16)") (class "Default")
      (node (ref "P6") (pin "16") (pinfunction "16_16") (pintype "input+no_connect"))
    )
  )
)
